# Launch-28020_V2.net
KiCad netlist of a schematic drawn in EAGLE
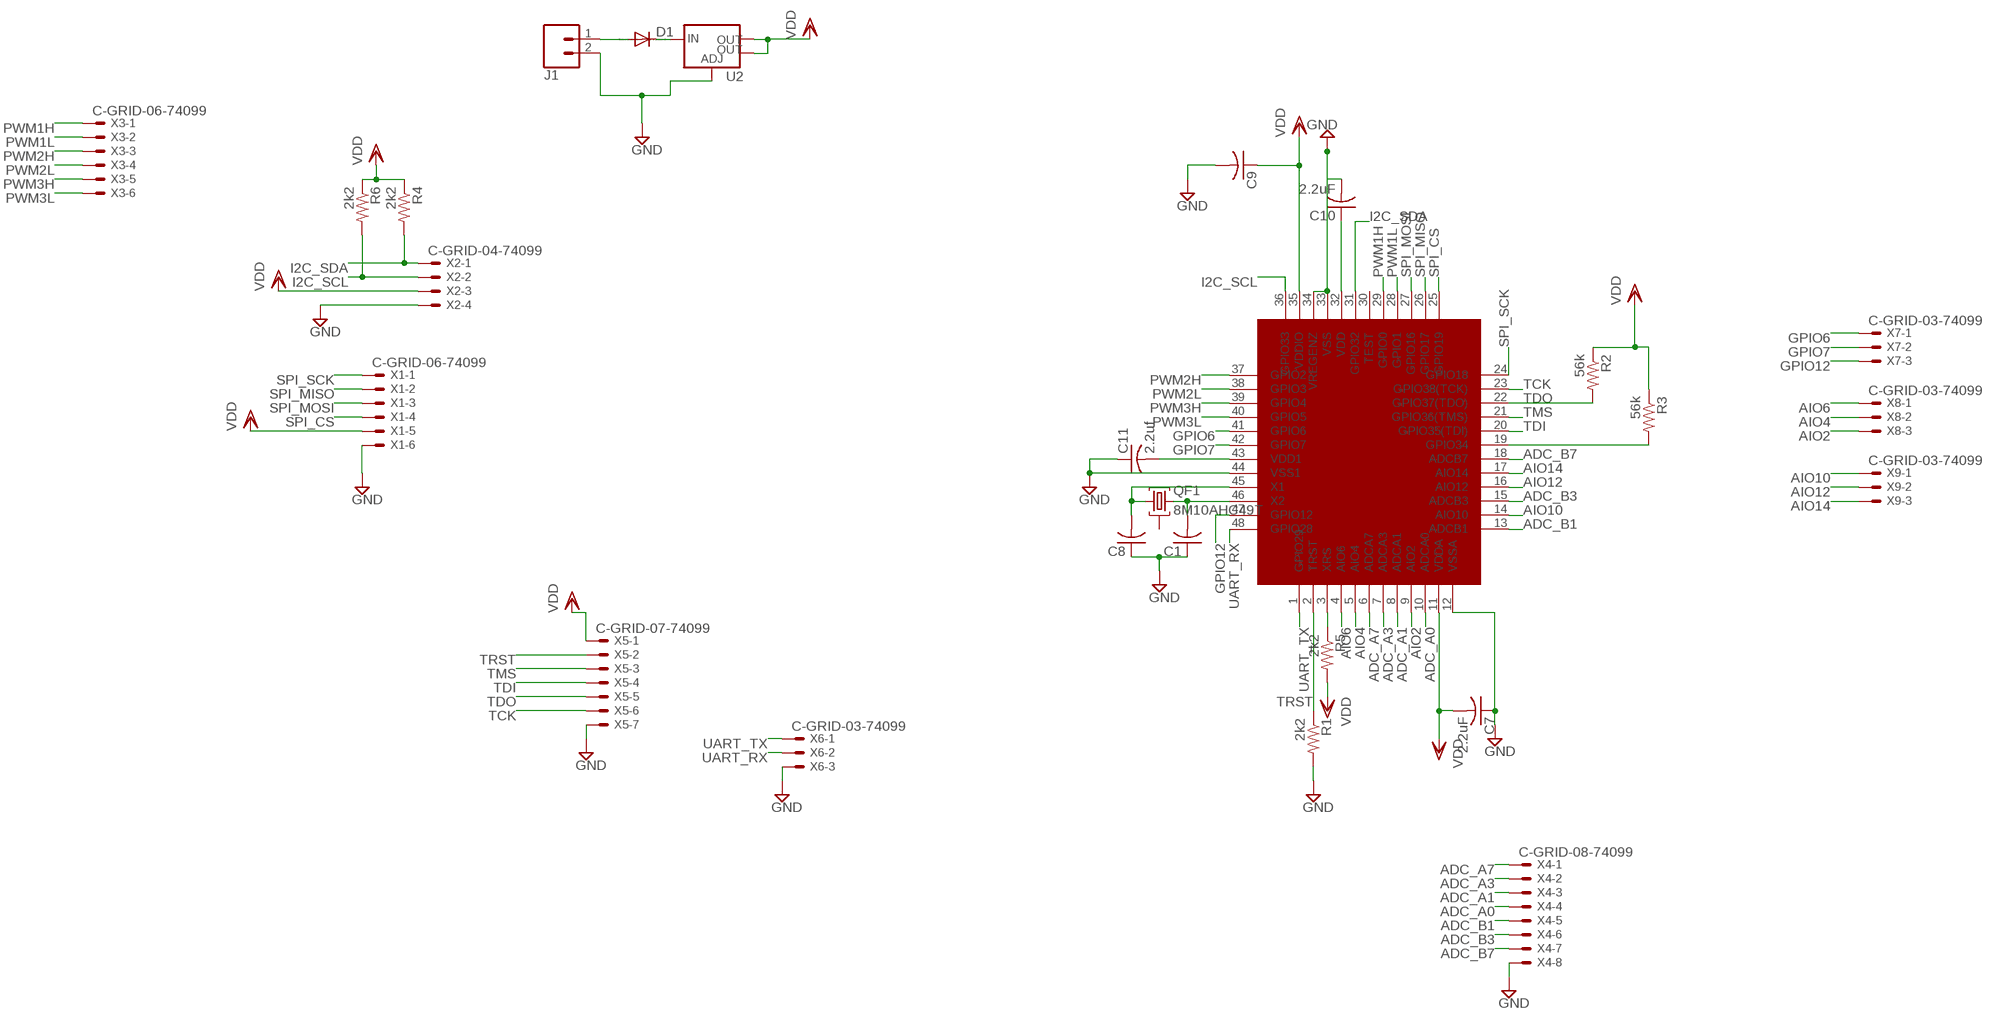
[diagram p0: schematic, sheet 1]

(export (version "E")
  (design (tool "Eeschema 10.0.6"))
  (components
    (comp (ref "C1")
      (value "C-USC1206")
      (footprint "eagle-import:C1206")
      (libsource (lib "eagle-import") (part "C-USC1206"))
    )
    (comp (ref "C7")
      (value "2.2uF")
      (footprint "eagle-import:C1206")
      (libsource (lib "eagle-import") (part "C-USC1206"))
    )
    (comp (ref "C8")
      (value "C-USC1206")
      (footprint "eagle-import:C1206")
      (libsource (lib "eagle-import") (part "C-USC1206"))
    )
    (comp (ref "C9")
      (value "C-USC1206")
      (footprint "eagle-import:C1206")
      (libsource (lib "eagle-import") (part "C-USC1206"))
    )
    (comp (ref "C10")
      (value "2.2uF")
      (footprint "eagle-import:C1206")
      (libsource (lib "eagle-import") (part "C-USC1206"))
    )
    (comp (ref "C11")
      (value "2.2uf")
      (footprint "eagle-import:C1206")
      (libsource (lib "eagle-import") (part "C-USC1206"))
    )
    (comp (ref "D1")
      (value "DIODE-SOD106-W")
      (footprint "eagle-import:SOD106-W")
      (libsource (lib "eagle-import") (part "DIODE-SOD106-W"))
    )
    (comp (ref "J1")
      (value "CONN_023.5MM-NO_SILK")
      (footprint "eagle-import:SCREWTERMINAL-3.5MM-2-NS")
      (libsource (lib "eagle-import") (part "CONN_023.5MM-NO_SILK"))
    )
    (comp (ref "QF1")
      (value "8M10AHC49T")
      (footprint "eagle-import:HC49U")
      (libsource (lib "eagle-import") (part "8M10AHC49T"))
    )
    (comp (ref "R1")
      (value "2k2")
      (footprint "eagle-import:M1206")
      (libsource (lib "eagle-import") (part "R-US_M1206"))
    )
    (comp (ref "R2")
      (value "56k")
      (footprint "eagle-import:M1206")
      (libsource (lib "eagle-import") (part "R-US_M1206"))
    )
    (comp (ref "R3")
      (value "56k")
      (footprint "eagle-import:M1206")
      (libsource (lib "eagle-import") (part "R-US_M1206"))
    )
    (comp (ref "R4")
      (value "2k2")
      (footprint "eagle-import:M1206")
      (libsource (lib "eagle-import") (part "R-US_M1206"))
    )
    (comp (ref "R5")
      (value "2k2")
      (footprint "eagle-import:M1206")
      (libsource (lib "eagle-import") (part "R-US_M1206"))
    )
    (comp (ref "R6")
      (value "2k2")
      (footprint "eagle-import:M1206")
      (libsource (lib "eagle-import") (part "R-US_M1206"))
    )
    (comp (ref "U$1")
      (value "TMS320F28020")
      (footprint "eagle-import:LQFP-48")
      (libsource (lib "eagle-import") (part "TMS320F28020"))
    )
    (comp (ref "U2")
      (value "V_REG_LM1117SOT223")
      (footprint "eagle-import:SOT223")
      (libsource (lib "eagle-import") (part "V_REG_LM1117SOT223"))
    )
    (comp (ref "X1")
      (value "C-GRID-06-74099")
      (footprint "eagle-import:74099-06")
      (libsource (lib "eagle-import") (part "C-GRID-06-74099"))
    )
    (comp (ref "X2")
      (value "C-GRID-04-74099")
      (footprint "eagle-import:74099-04")
      (libsource (lib "eagle-import") (part "C-GRID-04-74099"))
    )
    (comp (ref "X3")
      (value "C-GRID-06-74099")
      (footprint "eagle-import:74099-06")
      (libsource (lib "eagle-import") (part "C-GRID-06-74099"))
    )
    (comp (ref "X4")
      (value "C-GRID-08-74099")
      (footprint "eagle-import:74099-08")
      (libsource (lib "eagle-import") (part "C-GRID-08-74099"))
    )
    (comp (ref "X5")
      (value "C-GRID-07-74099")
      (footprint "eagle-import:74099-07")
      (libsource (lib "eagle-import") (part "C-GRID-07-74099"))
    )
    (comp (ref "X6")
      (value "C-GRID-03-74099")
      (footprint "eagle-import:74099-03")
      (libsource (lib "eagle-import") (part "C-GRID-03-74099"))
    )
    (comp (ref "X7")
      (value "C-GRID-03-74099")
      (footprint "eagle-import:74099-03")
      (libsource (lib "eagle-import") (part "C-GRID-03-74099"))
    )
    (comp (ref "X8")
      (value "C-GRID-03-74099")
      (footprint "eagle-import:74099-03")
      (libsource (lib "eagle-import") (part "C-GRID-03-74099"))
    )
    (comp (ref "X9")
      (value "C-GRID-03-74099")
      (footprint "eagle-import:74099-03")
      (libsource (lib "eagle-import") (part "C-GRID-03-74099"))
    )
  )
  (nets
    (net (code "1") (name "/ADC_A0") (class "Default")
      (node (ref "U$1") (pin "10") (pinfunction "ADCA0_10") (pintype "bidirectional"))
      (node (ref "X4") (pin "4") (pinfunction "S_4") (pintype "passive"))
    )
    (net (code "2") (name "/ADC_A1") (class "Default")
      (node (ref "U$1") (pin "8") (pinfunction "ADCA1_8") (pintype "bidirectional"))
      (node (ref "X4") (pin "3") (pinfunction "S_3") (pintype "passive"))
    )
    (net (code "3") (name "/ADC_A3") (class "Default")
      (node (ref "U$1") (pin "7") (pinfunction "ADCA3_7") (pintype "bidirectional"))
      (node (ref "X4") (pin "2") (pinfunction "S_2") (pintype "passive"))
    )
    (net (code "4") (name "/ADC_A7") (class "Default")
      (node (ref "U$1") (pin "6") (pinfunction "ADCA7_6") (pintype "bidirectional"))
      (node (ref "X4") (pin "1") (pinfunction "S_1") (pintype "passive"))
    )
    (net (code "5") (name "/ADC_B1") (class "Default")
      (node (ref "U$1") (pin "13") (pinfunction "ADCB1_13") (pintype "bidirectional"))
      (node (ref "X4") (pin "5") (pinfunction "S_5") (pintype "passive"))
    )
    (net (code "6") (name "/ADC_B3") (class "Default")
      (node (ref "U$1") (pin "15") (pinfunction "ADCB3_15") (pintype "bidirectional"))
      (node (ref "X4") (pin "6") (pinfunction "S_6") (pintype "passive"))
    )
    (net (code "7") (name "/ADC_B7") (class "Default")
      (node (ref "U$1") (pin "18") (pinfunction "ADCB7_18") (pintype "bidirectional"))
      (node (ref "X4") (pin "7") (pinfunction "S_7") (pintype "passive"))
    )
    (net (code "8") (name "/AIO2") (class "Default")
      (node (ref "U$1") (pin "9") (pinfunction "AIO2_9") (pintype "bidirectional"))
      (node (ref "X8") (pin "3") (pinfunction "S_3") (pintype "passive"))
    )
    (net (code "9") (name "/AIO4") (class "Default")
      (node (ref "U$1") (pin "5") (pinfunction "AIO4_5") (pintype "bidirectional"))
      (node (ref "X8") (pin "2") (pinfunction "S_2") (pintype "passive"))
    )
    (net (code "10") (name "/AIO6") (class "Default")
      (node (ref "U$1") (pin "4") (pinfunction "AIO6_4") (pintype "bidirectional"))
      (node (ref "X8") (pin "1") (pinfunction "S_1") (pintype "passive"))
    )
    (net (code "11") (name "/AIO10") (class "Default")
      (node (ref "U$1") (pin "14") (pinfunction "AIO10_14") (pintype "bidirectional"))
      (node (ref "X9") (pin "1") (pinfunction "S_1") (pintype "passive"))
    )
    (net (code "12") (name "/AIO12") (class "Default")
      (node (ref "U$1") (pin "16") (pinfunction "AIO12_16") (pintype "bidirectional"))
      (node (ref "X9") (pin "2") (pinfunction "S_2") (pintype "passive"))
    )
    (net (code "13") (name "/AIO14") (class "Default")
      (node (ref "U$1") (pin "17") (pinfunction "AIO14_17") (pintype "bidirectional"))
      (node (ref "X9") (pin "3") (pinfunction "S_3") (pintype "passive"))
    )
    (net (code "14") (name "/GPIO6") (class "Default")
      (node (ref "U$1") (pin "41") (pinfunction "GPIO6_41") (pintype "bidirectional"))
      (node (ref "X7") (pin "1") (pinfunction "S_1") (pintype "passive"))
    )
    (net (code "15") (name "/GPIO7") (class "Default")
      (node (ref "U$1") (pin "42") (pinfunction "GPIO7_42") (pintype "bidirectional"))
      (node (ref "X7") (pin "2") (pinfunction "S_2") (pintype "passive"))
    )
    (net (code "16") (name "/GPIO12") (class "Default")
      (node (ref "U$1") (pin "47") (pinfunction "GPIO12_47") (pintype "bidirectional"))
      (node (ref "X7") (pin "3") (pinfunction "S_3") (pintype "passive"))
    )
    (net (code "17") (name "/I2C_SCL") (class "Default")
      (node (ref "R6") (pin "2") (pinfunction "2_2") (pintype "passive"))
      (node (ref "U$1") (pin "36") (pinfunction "GPIO33_36") (pintype "bidirectional"))
      (node (ref "X2") (pin "2") (pinfunction "S_2") (pintype "passive"))
    )
    (net (code "18") (name "/I2C_SDA") (class "Default")
      (node (ref "R4") (pin "2") (pinfunction "2_2") (pintype "passive"))
      (node (ref "U$1") (pin "31") (pinfunction "GPIO32_31") (pintype "bidirectional"))
      (node (ref "X2") (pin "1") (pinfunction "S_1") (pintype "passive"))
    )
    (net (code "19") (name "/PWM1H") (class "Default")
      (node (ref "U$1") (pin "29") (pinfunction "GPIO0_29") (pintype "bidirectional"))
      (node (ref "X3") (pin "1") (pinfunction "S_1") (pintype "passive"))
    )
    (net (code "20") (name "/PWM1L") (class "Default")
      (node (ref "U$1") (pin "28") (pinfunction "GPIO1_28") (pintype "bidirectional"))
      (node (ref "X3") (pin "2") (pinfunction "S_2") (pintype "passive"))
    )
    (net (code "21") (name "/PWM2H") (class "Default")
      (node (ref "U$1") (pin "37") (pinfunction "GPIO2_37") (pintype "bidirectional"))
      (node (ref "X3") (pin "3") (pinfunction "S_3") (pintype "passive"))
    )
    (net (code "22") (name "/PWM2L") (class "Default")
      (node (ref "U$1") (pin "38") (pinfunction "GPIO3_38") (pintype "bidirectional"))
      (node (ref "X3") (pin "4") (pinfunction "S_4") (pintype "passive"))
    )
    (net (code "23") (name "/PWM3H") (class "Default")
      (node (ref "U$1") (pin "39") (pinfunction "GPIO4_39") (pintype "bidirectional"))
      (node (ref "X3") (pin "5") (pinfunction "S_5") (pintype "passive"))
    )
    (net (code "24") (name "/PWM3L") (class "Default")
      (node (ref "U$1") (pin "40") (pinfunction "GPIO5_40") (pintype "bidirectional"))
      (node (ref "X3") (pin "6") (pinfunction "S_6") (pintype "passive"))
    )
    (net (code "25") (name "/SPI_CS") (class "Default")
      (node (ref "U$1") (pin "25") (pinfunction "GPIO19_25") (pintype "bidirectional"))
      (node (ref "X1") (pin "4") (pinfunction "S_4") (pintype "passive"))
    )
    (net (code "26") (name "/SPI_MISO") (class "Default")
      (node (ref "U$1") (pin "26") (pinfunction "GPIO17_26") (pintype "bidirectional"))
      (node (ref "X1") (pin "2") (pinfunction "S_2") (pintype "passive"))
    )
    (net (code "27") (name "/SPI_MOSI") (class "Default")
      (node (ref "U$1") (pin "27") (pinfunction "GPIO16_27") (pintype "bidirectional"))
      (node (ref "X1") (pin "3") (pinfunction "S_3") (pintype "passive"))
    )
    (net (code "28") (name "/SPI_SCK") (class "Default")
      (node (ref "U$1") (pin "24") (pinfunction "GPIO18_24") (pintype "bidirectional"))
      (node (ref "X1") (pin "1") (pinfunction "S_1") (pintype "passive"))
    )
    (net (code "29") (name "/TCK") (class "Default")
      (node (ref "U$1") (pin "23") (pinfunction "GPIO38(TCK)_23") (pintype "bidirectional"))
      (node (ref "X5") (pin "6") (pinfunction "S_6") (pintype "passive"))
    )
    (net (code "30") (name "/TDI") (class "Default")
      (node (ref "U$1") (pin "20") (pinfunction "GPIO35(TDI)_20") (pintype "bidirectional"))
      (node (ref "X5") (pin "4") (pinfunction "S_4") (pintype "passive"))
    )
    (net (code "31") (name "/TDO") (class "Default")
      (node (ref "R2") (pin "2") (pinfunction "2_2") (pintype "passive"))
      (node (ref "U$1") (pin "22") (pinfunction "GPIO37(TDO)_22") (pintype "bidirectional"))
      (node (ref "X5") (pin "5") (pinfunction "S_5") (pintype "passive"))
    )
    (net (code "32") (name "/TMS") (class "Default")
      (node (ref "U$1") (pin "21") (pinfunction "GPIO36(TMS)_21") (pintype "bidirectional"))
      (node (ref "X5") (pin "3") (pinfunction "S_3") (pintype "passive"))
    )
    (net (code "33") (name "/TRST") (class "Default")
      (node (ref "R1") (pin "1") (pinfunction "1_1") (pintype "passive"))
      (node (ref "U$1") (pin "2") (pinfunction "TRST_2") (pintype "bidirectional"))
      (node (ref "X5") (pin "2") (pinfunction "S_2") (pintype "passive"))
    )
    (net (code "34") (name "/UART_RX") (class "Default")
      (node (ref "U$1") (pin "48") (pinfunction "GPIO28_48") (pintype "bidirectional"))
      (node (ref "X6") (pin "2") (pinfunction "S_2") (pintype "passive"))
    )
    (net (code "35") (name "/UART_TX") (class "Default")
      (node (ref "U$1") (pin "1") (pinfunction "GPIO29_1") (pintype "bidirectional"))
      (node (ref "X6") (pin "1") (pinfunction "S_1") (pintype "passive"))
    )
    (net (code "36") (name "GND") (class "Default")
      (node (ref "C1") (pin "1") (pinfunction "1_1") (pintype "passive"))
      (node (ref "C10") (pin "2") (pinfunction "2_2") (pintype "passive"))
      (node (ref "C11") (pin "1") (pinfunction "1_1") (pintype "passive"))
      (node (ref "C7") (pin "1") (pinfunction "1_1") (pintype "passive"))
      (node (ref "C8") (pin "1") (pinfunction "1_1") (pintype "passive"))
      (node (ref "C9") (pin "2") (pinfunction "2_2") (pintype "passive"))
      (node (ref "J1") (pin "2") (pinfunction "2_2") (pintype "passive"))
      (node (ref "R1") (pin "2") (pinfunction "2_2") (pintype "passive"))
      (node (ref "U$1") (pin "12") (pinfunction "VSSA_12") (pintype "bidirectional"))
      (node (ref "U$1") (pin "33") (pinfunction "VSS_33") (pintype "bidirectional"))
      (node (ref "U$1") (pin "34") (pinfunction "VREGENZ_34") (pintype "bidirectional"))
      (node (ref "U$1") (pin "44") (pinfunction "VSS1_44") (pintype "bidirectional"))
      (node (ref "U2") (pin "1") (pinfunction "ADJ_1") (pintype "input"))
      (node (ref "X1") (pin "6") (pinfunction "S_6") (pintype "passive"))
      (node (ref "X2") (pin "4") (pinfunction "S_4") (pintype "passive"))
      (node (ref "X4") (pin "8") (pinfunction "S_8") (pintype "passive"))
      (node (ref "X5") (pin "7") (pinfunction "S_7") (pintype "passive"))
      (node (ref "X6") (pin "3") (pinfunction "S_3") (pintype "passive"))
    )
    (net (code "37") (name "Net-(D1-PadA)") (class "Default")
      (node (ref "D1") (pin "A") (pinfunction "A_A") (pintype "passive"))
      (node (ref "J1") (pin "1") (pinfunction "1_1") (pintype "passive"))
    )
    (net (code "38") (name "Net-(U$1-GPIO34)") (class "Default")
      (node (ref "R3") (pin "2") (pinfunction "2_2") (pintype "passive"))
      (node (ref "U$1") (pin "19") (pinfunction "GPIO34_19") (pintype "bidirectional"))
    )
    (net (code "39") (name "Net-(U$1-VDD)") (class "Default")
      (node (ref "C10") (pin "1") (pinfunction "1_1") (pintype "passive"))
      (node (ref "U$1") (pin "32") (pinfunction "VDD_32") (pintype "bidirectional"))
    )
    (net (code "40") (name "Net-(U$1-VDD1)") (class "Default")
      (node (ref "C11") (pin "2") (pinfunction "2_2") (pintype "passive"))
      (node (ref "U$1") (pin "43") (pinfunction "VDD1_43") (pintype "bidirectional"))
    )
    (net (code "41") (name "Net-(U$1-X1)") (class "Default")
      (node (ref "C8") (pin "2") (pinfunction "2_2") (pintype "passive"))
      (node (ref "QF1") (pin "1") (pinfunction "1_1") (pintype "passive"))
      (node (ref "U$1") (pin "45") (pinfunction "X1_45") (pintype "bidirectional"))
    )
    (net (code "42") (name "Net-(U$1-X2)") (class "Default")
      (node (ref "C1") (pin "2") (pinfunction "2_2") (pintype "passive"))
      (node (ref "QF1") (pin "3") (pinfunction "3_3") (pintype "passive"))
      (node (ref "U$1") (pin "46") (pinfunction "X2_46") (pintype "bidirectional"))
    )
    (net (code "43") (name "Net-(U$1-XRS)") (class "Default")
      (node (ref "R5") (pin "1") (pinfunction "1_1") (pintype "passive"))
      (node (ref "U$1") (pin "3") (pinfunction "XRS_3") (pintype "bidirectional"))
    )
    (net (code "44") (name "Net-(U2-IN)") (class "Default")
      (node (ref "D1") (pin "C") (pinfunction "C_C") (pintype "passive"))
      (node (ref "U2") (pin "3") (pinfunction "IN_3") (pintype "input"))
    )
    (net (code "45") (name "VDD") (class "Default")
      (node (ref "C7") (pin "2") (pinfunction "2_2") (pintype "passive"))
      (node (ref "C9") (pin "1") (pinfunction "1_1") (pintype "passive"))
      (node (ref "R2") (pin "1") (pinfunction "1_1") (pintype "passive"))
      (node (ref "R3") (pin "1") (pinfunction "1_1") (pintype "passive"))
      (node (ref "R4") (pin "1") (pinfunction "1_1") (pintype "passive"))
      (node (ref "R5") (pin "2") (pinfunction "2_2") (pintype "passive"))
      (node (ref "R6") (pin "1") (pinfunction "1_1") (pintype "passive"))
      (node (ref "U$1") (pin "11") (pinfunction "VDDA_11") (pintype "bidirectional"))
      (node (ref "U$1") (pin "35") (pinfunction "VDDIO_35") (pintype "bidirectional"))
      (node (ref "U2") (pin "2") (pinfunction "OUT_2") (pintype "output"))
      (node (ref "U2") (pin "4") (pinfunction "OUT_4") (pintype "output"))
      (node (ref "X1") (pin "5") (pinfunction "S_5") (pintype "passive"))
      (node (ref "X2") (pin "3") (pinfunction "S_3") (pintype "passive"))
      (node (ref "X5") (pin "1") (pinfunction "S_1") (pintype "passive"))
    )
    (net (code "46") (name "unconnected-(QF1-Pad2)") (class "Default")
      (node (ref "QF1") (pin "2") (pinfunction "2_2") (pintype "passive"))
    )
    (net (code "47") (name "unconnected-(U$1-TEST-Pad30)") (class "Default")
      (node (ref "U$1") (pin "30") (pinfunction "TEST_30") (pintype "bidirectional"))
    )
  )
)
